# untitled.net
KiCad netlist of a schematic drawn in EAGLE
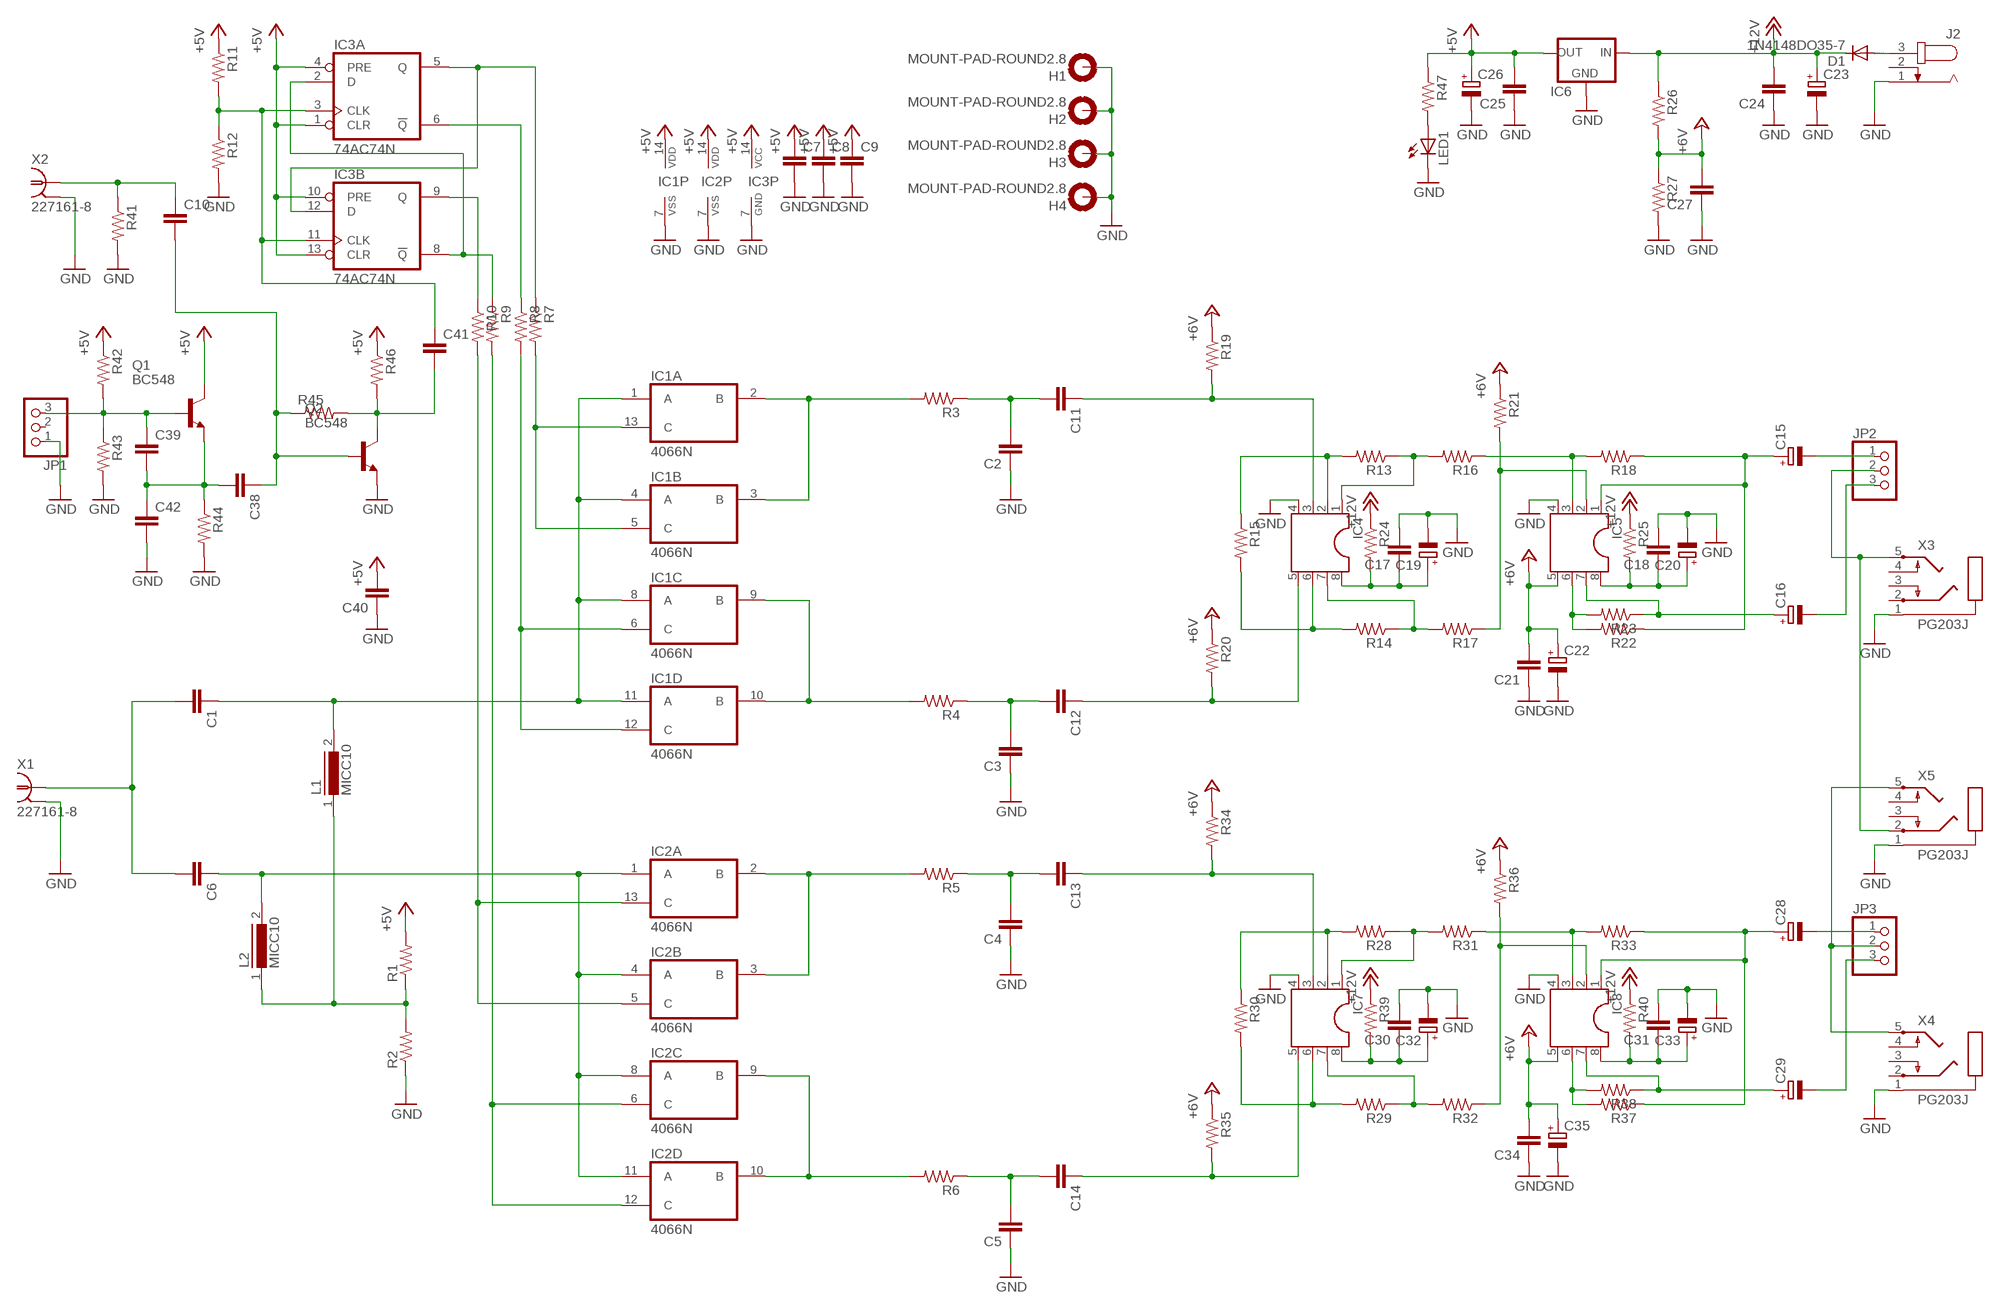
[diagram p0: schematic, sheet 1]

(export (version "E")
  (design (tool "Eeschema 10.0.6"))
  (components
    (comp (ref "C1")
      (value "C-EU050-025X075")
      (footprint "eagle-import:C050-025X075")
      (libsource (lib "eagle-import") (part "C-EU050-025X075"))
    )
    (comp (ref "C2")
      (value "C-EU050-025X075")
      (footprint "eagle-import:C050-025X075")
      (libsource (lib "eagle-import") (part "C-EU050-025X075"))
    )
    (comp (ref "C3")
      (value "C-EU050-025X075")
      (footprint "eagle-import:C050-025X075")
      (libsource (lib "eagle-import") (part "C-EU050-025X075"))
    )
    (comp (ref "C4")
      (value "C-EU050-025X075")
      (footprint "eagle-import:C050-025X075")
      (libsource (lib "eagle-import") (part "C-EU050-025X075"))
    )
    (comp (ref "C5")
      (value "C-EU050-025X075")
      (footprint "eagle-import:C050-025X075")
      (libsource (lib "eagle-import") (part "C-EU050-025X075"))
    )
    (comp (ref "C6")
      (value "C-EU050-025X075")
      (footprint "eagle-import:C050-025X075")
      (libsource (lib "eagle-import") (part "C-EU050-025X075"))
    )
    (comp (ref "C7")
      (value "C-EU050-025X075")
      (footprint "eagle-import:C050-025X075")
      (libsource (lib "eagle-import") (part "C-EU050-025X075"))
    )
    (comp (ref "C8")
      (value "C-EU050-025X075")
      (footprint "eagle-import:C050-025X075")
      (libsource (lib "eagle-import") (part "C-EU050-025X075"))
    )
    (comp (ref "C9")
      (value "C-EU050-025X075")
      (footprint "eagle-import:C050-025X075")
      (libsource (lib "eagle-import") (part "C-EU050-025X075"))
    )
    (comp (ref "C10")
      (value "C-EU050-025X075")
      (footprint "eagle-import:C050-025X075")
      (libsource (lib "eagle-import") (part "C-EU050-025X075"))
    )
    (comp (ref "C11")
      (value "C-EU050-025X075")
      (footprint "eagle-import:C050-025X075")
      (libsource (lib "eagle-import") (part "C-EU050-025X075"))
    )
    (comp (ref "C12")
      (value "C-EU050-025X075")
      (footprint "eagle-import:C050-025X075")
      (libsource (lib "eagle-import") (part "C-EU050-025X075"))
    )
    (comp (ref "C13")
      (value "C-EU050-025X075")
      (footprint "eagle-import:C050-025X075")
      (libsource (lib "eagle-import") (part "C-EU050-025X075"))
    )
    (comp (ref "C14")
      (value "C-EU050-025X075")
      (footprint "eagle-import:C050-025X075")
      (libsource (lib "eagle-import") (part "C-EU050-025X075"))
    )
    (comp (ref "C15")
      (value "CPOL-EUE5-6")
      (footprint "eagle-import:E5-6")
      (libsource (lib "eagle-import") (part "CPOL-EUE5-6"))
    )
    (comp (ref "C16")
      (value "CPOL-EUE5-6")
      (footprint "eagle-import:E5-6")
      (libsource (lib "eagle-import") (part "CPOL-EUE5-6"))
    )
    (comp (ref "C17")
      (value "C-EU050-025X075")
      (footprint "eagle-import:C050-025X075")
      (libsource (lib "eagle-import") (part "C-EU050-025X075"))
    )
    (comp (ref "C18")
      (value "C-EU050-025X075")
      (footprint "eagle-import:C050-025X075")
      (libsource (lib "eagle-import") (part "C-EU050-025X075"))
    )
    (comp (ref "C19")
      (value "CPOL-EUE5-6")
      (footprint "eagle-import:E5-6")
      (libsource (lib "eagle-import") (part "CPOL-EUE5-6"))
    )
    (comp (ref "C20")
      (value "CPOL-EUE5-6")
      (footprint "eagle-import:E5-6")
      (libsource (lib "eagle-import") (part "CPOL-EUE5-6"))
    )
    (comp (ref "C21")
      (value "C-EU050-025X075")
      (footprint "eagle-import:C050-025X075")
      (libsource (lib "eagle-import") (part "C-EU050-025X075"))
    )
    (comp (ref "C22")
      (value "CPOL-EUE5-6")
      (footprint "eagle-import:E5-6")
      (libsource (lib "eagle-import") (part "CPOL-EUE5-6"))
    )
    (comp (ref "C23")
      (value "CPOL-EUE5-6")
      (footprint "eagle-import:E5-6")
      (libsource (lib "eagle-import") (part "CPOL-EUE5-6"))
    )
    (comp (ref "C24")
      (value "C-EU050-025X075")
      (footprint "eagle-import:C050-025X075")
      (libsource (lib "eagle-import") (part "C-EU050-025X075"))
    )
    (comp (ref "C25")
      (value "C-EU050-025X075")
      (footprint "eagle-import:C050-025X075")
      (libsource (lib "eagle-import") (part "C-EU050-025X075"))
    )
    (comp (ref "C26")
      (value "CPOL-EUE5-6")
      (footprint "eagle-import:E5-6")
      (libsource (lib "eagle-import") (part "CPOL-EUE5-6"))
    )
    (comp (ref "C27")
      (value "C-EU050-025X075")
      (footprint "eagle-import:C050-025X075")
      (libsource (lib "eagle-import") (part "C-EU050-025X075"))
    )
    (comp (ref "C28")
      (value "CPOL-EUE5-6")
      (footprint "eagle-import:E5-6")
      (libsource (lib "eagle-import") (part "CPOL-EUE5-6"))
    )
    (comp (ref "C29")
      (value "CPOL-EUE5-6")
      (footprint "eagle-import:E5-6")
      (libsource (lib "eagle-import") (part "CPOL-EUE5-6"))
    )
    (comp (ref "C30")
      (value "C-EU050-025X075")
      (footprint "eagle-import:C050-025X075")
      (libsource (lib "eagle-import") (part "C-EU050-025X075"))
    )
    (comp (ref "C31")
      (value "C-EU050-025X075")
      (footprint "eagle-import:C050-025X075")
      (libsource (lib "eagle-import") (part "C-EU050-025X075"))
    )
    (comp (ref "C32")
      (value "CPOL-EUE5-6")
      (footprint "eagle-import:E5-6")
      (libsource (lib "eagle-import") (part "CPOL-EUE5-6"))
    )
    (comp (ref "C33")
      (value "CPOL-EUE5-6")
      (footprint "eagle-import:E5-6")
      (libsource (lib "eagle-import") (part "CPOL-EUE5-6"))
    )
    (comp (ref "C34")
      (value "C-EU050-025X075")
      (footprint "eagle-import:C050-025X075")
      (libsource (lib "eagle-import") (part "C-EU050-025X075"))
    )
    (comp (ref "C35")
      (value "CPOL-EUE5-6")
      (footprint "eagle-import:E5-6")
      (libsource (lib "eagle-import") (part "CPOL-EUE5-6"))
    )
    (comp (ref "C38")
      (value "C-EU050-025X075")
      (footprint "eagle-import:C050-025X075")
      (libsource (lib "eagle-import") (part "C-EU050-025X075"))
    )
    (comp (ref "C39")
      (value "C-EU025-025X050")
      (footprint "eagle-import:C025-025X050")
      (libsource (lib "eagle-import") (part "C-EU025-025X050"))
    )
    (comp (ref "C40")
      (value "C-EU050-025X075")
      (footprint "eagle-import:C050-025X075")
      (libsource (lib "eagle-import") (part "C-EU050-025X075"))
    )
    (comp (ref "C41")
      (value "C-EU075-032X103")
      (footprint "eagle-import:C075-032X103")
      (libsource (lib "eagle-import") (part "C-EU075-032X103"))
    )
    (comp (ref "C42")
      (value "C-EU025-025X050")
      (footprint "eagle-import:C025-025X050")
      (libsource (lib "eagle-import") (part "C-EU025-025X050"))
    )
    (comp (ref "D1")
      (value "1N4148DO35-7")
      (footprint "eagle-import:DO35-7")
      (libsource (lib "eagle-import") (part "1N4148DO35-7"))
    )
    (comp (ref "H1")
      (value "MOUNT-PAD-ROUND2.8")
      (footprint "eagle-import:2,8-PAD")
      (libsource (lib "eagle-import") (part "MOUNT-PAD-ROUND2.8"))
    )
    (comp (ref "H2")
      (value "MOUNT-PAD-ROUND2.8")
      (footprint "eagle-import:2,8-PAD")
      (libsource (lib "eagle-import") (part "MOUNT-PAD-ROUND2.8"))
    )
    (comp (ref "H3")
      (value "MOUNT-PAD-ROUND2.8")
      (footprint "eagle-import:2,8-PAD")
      (libsource (lib "eagle-import") (part "MOUNT-PAD-ROUND2.8"))
    )
    (comp (ref "H4")
      (value "MOUNT-PAD-ROUND2.8")
      (footprint "eagle-import:2,8-PAD")
      (libsource (lib "eagle-import") (part "MOUNT-PAD-ROUND2.8"))
    )
    (comp (ref "IC1")
      (value "4066N")
      (footprint "eagle-import:DIL14")
      (libsource (lib "eagle-import") (part "4066N"))
    )
    (comp (ref "IC2")
      (value "4066N")
      (footprint "eagle-import:DIL14")
      (libsource (lib "eagle-import") (part "4066N"))
    )
    (comp (ref "IC3")
      (value "74AC74N")
      (footprint "eagle-import:DIL14")
      (libsource (lib "eagle-import") (part "7474NAC"))
    )
    (comp (ref "IC4")
      (value "DIL8")
      (footprint "eagle-import:DIL08")
      (libsource (lib "eagle-import") (part "DIL8"))
    )
    (comp (ref "IC5")
      (value "DIL8")
      (footprint "eagle-import:DIL08")
      (libsource (lib "eagle-import") (part "DIL8"))
    )
    (comp (ref "IC6")
      (value "78XXS")
      (footprint "eagle-import:78XXS")
      (libsource (lib "eagle-import") (part "78XXS"))
    )
    (comp (ref "IC7")
      (value "DIL8")
      (footprint "eagle-import:DIL08")
      (libsource (lib "eagle-import") (part "DIL8"))
    )
    (comp (ref "IC8")
      (value "DIL8")
      (footprint "eagle-import:DIL08")
      (libsource (lib "eagle-import") (part "DIL8"))
    )
    (comp (ref "J2")
      (value "JACK-PLUG0")
      (footprint "eagle-import:SPC4077")
      (libsource (lib "eagle-import") (part "JACK-PLUG0"))
    )
    (comp (ref "JP1")
      (value "PINHD-1X3")
      (footprint "eagle-import:1X03")
      (libsource (lib "eagle-import") (part "PINHD-1X3"))
    )
    (comp (ref "JP2")
      (value "PINHD-1X3")
      (footprint "eagle-import:1X03")
      (libsource (lib "eagle-import") (part "PINHD-1X3"))
    )
    (comp (ref "JP3")
      (value "PINHD-1X3")
      (footprint "eagle-import:1X03")
      (libsource (lib "eagle-import") (part "PINHD-1X3"))
    )
    (comp (ref "L1")
      (value "MICC10")
      (footprint "eagle-import:MICC10")
      (libsource (lib "eagle-import") (part "MICC10"))
    )
    (comp (ref "L2")
      (value "MICC10")
      (footprint "eagle-import:MICC10")
      (libsource (lib "eagle-import") (part "MICC10"))
    )
    (comp (ref "LED1")
      (value "LED3MM")
      (footprint "eagle-import:LED3MM")
      (libsource (lib "eagle-import") (part "LED3MM"))
    )
    (comp (ref "Q1")
      (value "BC548")
      (footprint "eagle-import:TO92-EBC")
      (libsource (lib "eagle-import") (part "BC548"))
    )
    (comp (ref "Q2")
      (value "BC548")
      (footprint "eagle-import:TO92-EBC")
      (libsource (lib "eagle-import") (part "BC548"))
    )
    (comp (ref "R1")
      (value "R-US_0207/7")
      (footprint "eagle-import:0207_7")
      (libsource (lib "eagle-import") (part "R-US_0207/7"))
    )
    (comp (ref "R2")
      (value "R-US_0207/7")
      (footprint "eagle-import:0207_7")
      (libsource (lib "eagle-import") (part "R-US_0207/7"))
    )
    (comp (ref "R3")
      (value "R-US_0207/7")
      (footprint "eagle-import:0207_7")
      (libsource (lib "eagle-import") (part "R-US_0207/7"))
    )
    (comp (ref "R4")
      (value "R-US_0207/7")
      (footprint "eagle-import:0207_7")
      (libsource (lib "eagle-import") (part "R-US_0207/7"))
    )
    (comp (ref "R5")
      (value "R-US_0207/7")
      (footprint "eagle-import:0207_7")
      (libsource (lib "eagle-import") (part "R-US_0207/7"))
    )
    (comp (ref "R6")
      (value "R-US_0207/7")
      (footprint "eagle-import:0207_7")
      (libsource (lib "eagle-import") (part "R-US_0207/7"))
    )
    (comp (ref "R7")
      (value "R-US_0207/7")
      (footprint "eagle-import:0207_7")
      (libsource (lib "eagle-import") (part "R-US_0207/7"))
    )
    (comp (ref "R8")
      (value "R-US_0207/7")
      (footprint "eagle-import:0207_7")
      (libsource (lib "eagle-import") (part "R-US_0207/7"))
    )
    (comp (ref "R9")
      (value "R-US_0207/7")
      (footprint "eagle-import:0207_7")
      (libsource (lib "eagle-import") (part "R-US_0207/7"))
    )
    (comp (ref "R10")
      (value "R-US_0207/7")
      (footprint "eagle-import:0207_7")
      (libsource (lib "eagle-import") (part "R-US_0207/7"))
    )
    (comp (ref "R11")
      (value "R-US_0207/7")
      (footprint "eagle-import:0207_7")
      (libsource (lib "eagle-import") (part "R-US_0207/7"))
    )
    (comp (ref "R12")
      (value "R-US_0207/7")
      (footprint "eagle-import:0207_7")
      (libsource (lib "eagle-import") (part "R-US_0207/7"))
    )
    (comp (ref "R13")
      (value "R-US_0207/7")
      (footprint "eagle-import:0207_7")
      (libsource (lib "eagle-import") (part "R-US_0207/7"))
    )
    (comp (ref "R14")
      (value "R-US_0207/7")
      (footprint "eagle-import:0207_7")
      (libsource (lib "eagle-import") (part "R-US_0207/7"))
    )
    (comp (ref "R15")
      (value "R-US_0207/7")
      (footprint "eagle-import:0207_7")
      (libsource (lib "eagle-import") (part "R-US_0207/7"))
    )
    (comp (ref "R16")
      (value "R-US_0207/7")
      (footprint "eagle-import:0207_7")
      (libsource (lib "eagle-import") (part "R-US_0207/7"))
    )
    (comp (ref "R17")
      (value "R-US_0207/7")
      (footprint "eagle-import:0207_7")
      (libsource (lib "eagle-import") (part "R-US_0207/7"))
    )
    (comp (ref "R18")
      (value "R-US_0207/7")
      (footprint "eagle-import:0207_7")
      (libsource (lib "eagle-import") (part "R-US_0207/7"))
    )
    (comp (ref "R19")
      (value "R-US_0207/7")
      (footprint "eagle-import:0207_7")
      (libsource (lib "eagle-import") (part "R-US_0207/7"))
    )
    (comp (ref "R20")
      (value "R-US_0207/7")
      (footprint "eagle-import:0207_7")
      (libsource (lib "eagle-import") (part "R-US_0207/7"))
    )
    (comp (ref "R21")
      (value "R-US_0207/7")
      (footprint "eagle-import:0207_7")
      (libsource (lib "eagle-import") (part "R-US_0207/7"))
    )
    (comp (ref "R22")
      (value "R-US_0207/7")
      (footprint "eagle-import:0207_7")
      (libsource (lib "eagle-import") (part "R-US_0207/7"))
    )
    (comp (ref "R23")
      (value "R-US_0207/7")
      (footprint "eagle-import:0207_7")
      (libsource (lib "eagle-import") (part "R-US_0207/7"))
    )
    (comp (ref "R24")
      (value "R-US_0207/7")
      (footprint "eagle-import:0207_7")
      (libsource (lib "eagle-import") (part "R-US_0207/7"))
    )
    (comp (ref "R25")
      (value "R-US_0207/7")
      (footprint "eagle-import:0207_7")
      (libsource (lib "eagle-import") (part "R-US_0207/7"))
    )
    (comp (ref "R26")
      (value "R-US_0207/7")
      (footprint "eagle-import:0207_7")
      (libsource (lib "eagle-import") (part "R-US_0207/7"))
    )
    (comp (ref "R27")
      (value "R-US_0207/7")
      (footprint "eagle-import:0207_7")
      (libsource (lib "eagle-import") (part "R-US_0207/7"))
    )
    (comp (ref "R28")
      (value "R-US_0207/7")
      (footprint "eagle-import:0207_7")
      (libsource (lib "eagle-import") (part "R-US_0207/7"))
    )
    (comp (ref "R29")
      (value "R-US_0207/7")
      (footprint "eagle-import:0207_7")
      (libsource (lib "eagle-import") (part "R-US_0207/7"))
    )
    (comp (ref "R30")
      (value "R-US_0207/7")
      (footprint "eagle-import:0207_7")
      (libsource (lib "eagle-import") (part "R-US_0207/7"))
    )
    (comp (ref "R31")
      (value "R-US_0207/7")
      (footprint "eagle-import:0207_7")
      (libsource (lib "eagle-import") (part "R-US_0207/7"))
    )
    (comp (ref "R32")
      (value "R-US_0207/7")
      (footprint "eagle-import:0207_7")
      (libsource (lib "eagle-import") (part "R-US_0207/7"))
    )
    (comp (ref "R33")
      (value "R-US_0207/7")
      (footprint "eagle-import:0207_7")
      (libsource (lib "eagle-import") (part "R-US_0207/7"))
    )
    (comp (ref "R34")
      (value "R-US_0207/7")
      (footprint "eagle-import:0207_7")
      (libsource (lib "eagle-import") (part "R-US_0207/7"))
    )
    (comp (ref "R35")
      (value "R-US_0207/7")
      (footprint "eagle-import:0207_7")
      (libsource (lib "eagle-import") (part "R-US_0207/7"))
    )
    (comp (ref "R36")
      (value "R-US_0207/7")
      (footprint "eagle-import:0207_7")
      (libsource (lib "eagle-import") (part "R-US_0207/7"))
    )
    (comp (ref "R37")
      (value "R-US_0207/7")
      (footprint "eagle-import:0207_7")
      (libsource (lib "eagle-import") (part "R-US_0207/7"))
    )
    (comp (ref "R38")
      (value "R-US_0207/7")
      (footprint "eagle-import:0207_7")
      (libsource (lib "eagle-import") (part "R-US_0207/7"))
    )
    (comp (ref "R39")
      (value "R-US_0207/7")
      (footprint "eagle-import:0207_7")
      (libsource (lib "eagle-import") (part "R-US_0207/7"))
    )
    (comp (ref "R40")
      (value "R-US_0207/7")
      (footprint "eagle-import:0207_7")
      (libsource (lib "eagle-import") (part "R-US_0207/7"))
    )
    (comp (ref "R41")
      (value "R-US_0207/7")
      (footprint "eagle-import:0207_7")
      (libsource (lib "eagle-import") (part "R-US_0207/7"))
    )
    (comp (ref "R42")
      (value "R-US_0207/7")
      (footprint "eagle-import:0207_7")
      (libsource (lib "eagle-import") (part "R-US_0207/7"))
    )
    (comp (ref "R43")
      (value "R-US_0207/7")
      (footprint "eagle-import:0207_7")
      (libsource (lib "eagle-import") (part "R-US_0207/7"))
    )
    (comp (ref "R44")
      (value "R-US_0207/7")
      (footprint "eagle-import:0207_7")
      (libsource (lib "eagle-import") (part "R-US_0207/7"))
    )
    (comp (ref "R45")
      (value "R-US_0207/7")
      (footprint "eagle-import:0207_7")
      (libsource (lib "eagle-import") (part "R-US_0207/7"))
    )
    (comp (ref "R46")
      (value "R-US_0207/7")
      (footprint "eagle-import:0207_7")
      (libsource (lib "eagle-import") (part "R-US_0207/7"))
    )
    (comp (ref "R47")
      (value "R-US_0207/7")
      (footprint "eagle-import:0207_7")
      (libsource (lib "eagle-import") (part "R-US_0207/7"))
    )
    (comp (ref "X1")
      (value "227161-8")
      (footprint "eagle-import:AMP_227161")
      (libsource (lib "eagle-import") (part "?227161-8"))
    )
    (comp (ref "X2")
      (value "227161-8")
      (footprint "eagle-import:AMP_227161")
      (libsource (lib "eagle-import") (part "?227161-8"))
    )
    (comp (ref "X3")
      (value "PG203J")
      (footprint "eagle-import:PG203J")
      (libsource (lib "eagle-import") (part "PG203J"))
    )
    (comp (ref "X4")
      (value "PG203J")
      (footprint "eagle-import:PG203J")
      (libsource (lib "eagle-import") (part "PG203J"))
    )
    (comp (ref "X5")
      (value "PG203J")
      (footprint "eagle-import:PG203J")
      (libsource (lib "eagle-import") (part "PG203J"))
    )
  )
  (nets
    (net (code "1") (name "+5V") (class "Default")
      (node (ref "C25") (pin "2") (pinfunction "2_2") (pintype "passive"))
      (node (ref "C26") (pin "+") (pinfunction "+_+") (pintype "passive"))
      (node (ref "C40") (pin "2") (pinfunction "2_2") (pintype "passive"))
      (node (ref "C7") (pin "1") (pinfunction "1_1") (pintype "passive"))
      (node (ref "C8") (pin "1") (pinfunction "1_1") (pintype "passive"))
      (node (ref "C9") (pin "1") (pinfunction "1_1") (pintype "passive"))
      (node (ref "IC1") (pin "14") (pinfunction "VDD_14") (pintype "power_in"))
      (node (ref "IC2") (pin "14") (pinfunction "VDD_14") (pintype "power_in"))
      (node (ref "IC3") (pin "1") (pinfunction "CLR_1") (pintype "input"))
      (node (ref "IC3") (pin "10") (pinfunction "PRE_10") (pintype "input"))
      (node (ref "IC3") (pin "13") (pinfunction "CLR_13") (pintype "input"))
      (node (ref "IC3") (pin "14") (pinfunction "VCC_14") (pintype "power_in"))
      (node (ref "IC3") (pin "4") (pinfunction "PRE_4") (pintype "input"))
      (node (ref "IC6") (pin "OUT") (pinfunction "OUT_OUT") (pintype "passive"))
      (node (ref "Q1") (pin "C") (pinfunction "C_C") (pintype "passive"))
      (node (ref "R1") (pin "2") (pinfunction "2_2") (pintype "passive"))
      (node (ref "R11") (pin "1") (pinfunction "1_1") (pintype "passive"))
      (node (ref "R42") (pin "1") (pinfunction "1_1") (pintype "passive"))
      (node (ref "R46") (pin "1") (pinfunction "1_1") (pintype "passive"))
      (node (ref "R47") (pin "1") (pinfunction "1_1") (pintype "passive"))
    )
    (net (code "2") (name "+6V") (class "Default")
      (node (ref "C21") (pin "2") (pinfunction "2_2") (pintype "passive"))
      (node (ref "C22") (pin "+") (pinfunction "+_+") (pintype "passive"))
      (node (ref "C27") (pin "2") (pinfunction "2_2") (pintype "passive"))
      (node (ref "C34") (pin "2") (pinfunction "2_2") (pintype "passive"))
      (node (ref "C35") (pin "+") (pinfunction "+_+") (pintype "passive"))
      (node (ref "IC5") (pin "5") (pinfunction "5_5") (pintype "passive"))
      (node (ref "IC8") (pin "5") (pinfunction "5_5") (pintype "passive"))
      (node (ref "R19") (pin "1") (pinfunction "1_1") (pintype "passive"))
      (node (ref "R20") (pin "1") (pinfunction "1_1") (pintype "passive"))
      (node (ref "R21") (pin "1") (pinfunction "1_1") (pintype "passive"))
      (node (ref "R26") (pin "2") (pinfunction "2_2") (pintype "passive"))
      (node (ref "R27") (pin "1") (pinfunction "1_1") (pintype "passive"))
      (node (ref "R34") (pin "1") (pinfunction "1_1") (pintype "passive"))
      (node (ref "R35") (pin "1") (pinfunction "1_1") (pintype "passive"))
      (node (ref "R36") (pin "1") (pinfunction "1_1") (pintype "passive"))
    )
    (net (code "3") (name "+12V") (class "Default")
      (node (ref "C23") (pin "+") (pinfunction "+_+") (pintype "passive"))
      (node (ref "C24") (pin "2") (pinfunction "2_2") (pintype "passive"))
      (node (ref "D1") (pin "C") (pinfunction "C_C") (pintype "passive"))
      (node (ref "IC6") (pin "IN") (pinfunction "IN_IN") (pintype "input"))
      (node (ref "R24") (pin "1") (pinfunction "1_1") (pintype "passive"))
      (node (ref "R25") (pin "1") (pinfunction "1_1") (pintype "passive"))
      (node (ref "R26") (pin "1") (pinfunction "1_1") (pintype "passive"))
      (node (ref "R39") (pin "1") (pinfunction "1_1") (pintype "passive"))
      (node (ref "R40") (pin "1") (pinfunction "1_1") (pintype "passive"))
    )
    (net (code "4") (name "GND") (class "Default")
      (node (ref "C17") (pin "2") (pinfunction "2_2") (pintype "passive"))
      (node (ref "C18") (pin "2") (pinfunction "2_2") (pintype "passive"))
      (node (ref "C19") (pin "-") (pinfunction "-_-") (pintype "passive"))
      (node (ref "C2") (pin "1") (pinfunction "1_1") (pintype "passive"))
      (node (ref "C20") (pin "-") (pinfunction "-_-") (pintype "passive"))
      (node (ref "C21") (pin "1") (pinfunction "1_1") (pintype "passive"))
      (node (ref "C22") (pin "-") (pinfunction "-_-") (pintype "passive"))
      (node (ref "C23") (pin "-") (pinfunction "-_-") (pintype "passive"))
      (node (ref "C24") (pin "1") (pinfunction "1_1") (pintype "passive"))
      (node (ref "C25") (pin "1") (pinfunction "1_1") (pintype "passive"))
      (node (ref "C26") (pin "-") (pinfunction "-_-") (pintype "passive"))
      (node (ref "C27") (pin "1") (pinfunction "1_1") (pintype "passive"))
      (node (ref "C3") (pin "1") (pinfunction "1_1") (pintype "passive"))
      (node (ref "C30") (pin "2") (pinfunction "2_2") (pintype "passive"))
      (node (ref "C31") (pin "2") (pinfunction "2_2") (pintype "passive"))
      (node (ref "C32") (pin "-") (pinfunction "-_-") (pintype "passive"))
      (node (ref "C33") (pin "-") (pinfunction "-_-") (pintype "passive"))
      (node (ref "C34") (pin "1") (pinfunction "1_1") (pintype "passive"))
      (node (ref "C35") (pin "-") (pinfunction "-_-") (pintype "passive"))
      (node (ref "C4") (pin "1") (pinfunction "1_1") (pintype "passive"))
      (node (ref "C40") (pin "1") (pinfunction "1_1") (pintype "passive"))
      (node (ref "C42") (pin "2") (pinfunction "2_2") (pintype "passive"))
      (node (ref "C5") (pin "1") (pinfunction "1_1") (pintype "passive"))
      (node (ref "C7") (pin "2") (pinfunction "2_2") (pintype "passive"))
      (node (ref "C8") (pin "2") (pinfunction "2_2") (pintype "passive"))
      (node (ref "C9") (pin "2") (pinfunction "2_2") (pintype "passive"))
      (node (ref "H1") (pin "B2,8") (pinfunction "MOUNT_B2,8") (pintype "passive"))
      (node (ref "H2") (pin "B2,8") (pinfunction "MOUNT_B2,8") (pintype "passive"))
      (node (ref "H3") (pin "B2,8") (pinfunction "MOUNT_B2,8") (pintype "passive"))
      (node (ref "H4") (pin "B2,8") (pinfunction "MOUNT_B2,8") (pintype "passive"))
      (node (ref "IC1") (pin "7") (pinfunction "VSS_7") (pintype "power_in"))
      (node (ref "IC2") (pin "7") (pinfunction "VSS_7") (pintype "power_in"))
      (node (ref "IC3") (pin "7") (pinfunction "GND_7") (pintype "power_in"))
      (node (ref "IC4") (pin "4") (pinfunction "4_4") (pintype "passive"))
      (node (ref "IC5") (pin "4") (pinfunction "4_4") (pintype "passive"))
      (node (ref "IC6") (pin "GND") (pinfunction "GND_GND") (pintype "input"))
      (node (ref "IC7") (pin "4") (pinfunction "4_4") (pintype "passive"))
      (node (ref "IC8") (pin "4") (pinfunction "4_4") (pintype "passive"))
      (node (ref "J2") (pin "1") (pinfunction "1_1") (pintype "passive"))
      (node (ref "JP1") (pin "1") (pinfunction "1_1") (pintype "passive"))
      (node (ref "LED1") (pin "K") (pinfunction "C_K") (pintype "passive"))
      (node (ref "Q2") (pin "E") (pinfunction "E_E") (pintype "passive"))
      (node (ref "R12") (pin "2") (pinfunction "2_2") (pintype "passive"))
      (node (ref "R2") (pin "1") (pinfunction "1_1") (pintype "passive"))
      (node (ref "R27") (pin "2") (pinfunction "2_2") (pintype "passive"))
      (node (ref "R41") (pin "2") (pinfunction "2_2") (pintype "passive"))
      (node (ref "R43") (pin "2") (pinfunction "2_2") (pintype "passive"))
      (node (ref "R44") (pin "2") (pinfunction "2_2") (pintype "passive"))
      (node (ref "X1") (pin "2") (pinfunction "2_2") (pintype "passive"))
      (node (ref "X2") (pin "2") (pinfunction "2_2") (pintype "passive"))
      (node (ref "X3") (pin "1") (pinfunction "1_1") (pintype "passive"))
      (node (ref "X4") (pin "1") (pinfunction "1_1") (pintype "passive"))
      (node (ref "X5") (pin "1") (pinfunction "1_1") (pintype "passive"))
    )
    (net (code "5") (name "Net-(C1-Pad2)") (class "Default")
      (node (ref "C1") (pin "2") (pinfunction "2_2") (pintype "passive"))
      (node (ref "C6") (pin "2") (pinfunction "2_2") (pintype "passive"))
      (node (ref "X1") (pin "1") (pinfunction "1_1") (pintype "passive"))
    )
    (net (code "6") (name "Net-(C10-Pad1)") (class "Default")
      (node (ref "C10") (pin "1") (pinfunction "1_1") (pintype "passive"))
      (node (ref "R41") (pin "1") (pinfunction "1_1") (pintype "passive"))
      (node (ref "X2") (pin "1") (pinfunction "1_1") (pintype "passive"))
    )
    (net (code "7") (name "Net-(C10-Pad2)") (class "Default")
      (node (ref "C10") (pin "2") (pinfunction "2_2") (pintype "passive"))
      (node (ref "C38") (pin "1") (pinfunction "1_1") (pintype "passive"))
      (node (ref "Q2") (pin "B") (pinfunction "B_B") (pintype "passive"))
      (node (ref "R45") (pin "1") (pinfunction "1_1") (pintype "passive"))
    )
    (net (code "8") (name "Net-(C11-Pad1)") (class "Default")
      (node (ref "C11") (pin "1") (pinfunction "1_1") (pintype "passive"))
      (node (ref "IC4") (pin "3") (pinfunction "3_3") (pintype "passive"))
      (node (ref "R19") (pin "2") (pinfunction "2_2") (pintype "passive"))
    )
    (net (code "9") (name "Net-(C11-Pad2)") (class "Default")
      (node (ref "C11") (pin "2") (pinfunction "2_2") (pintype "passive"))
      (node (ref "C2") (pin "2") (pinfunction "2_2") (pintype "passive"))
      (node (ref "R3") (pin "1") (pinfunction "1_1") (pintype "passive"))
    )
    (net (code "10") (name "Net-(C12-Pad1)") (class "Default")
      (node (ref "C12") (pin "1") (pinfunction "1_1") (pintype "passive"))
      (node (ref "IC4") (pin "5") (pinfunction "5_5") (pintype "passive"))
      (node (ref "R20") (pin "2") (pinfunction "2_2") (pintype "passive"))
    )
    (net (code "11") (name "Net-(C12-Pad2)") (class "Default")
      (node (ref "C12") (pin "2") (pinfunction "2_2") (pintype "passive"))
      (node (ref "C3") (pin "2") (pinfunction "2_2") (pintype "passive"))
      (node (ref "R4") (pin "1") (pinfunction "1_1") (pintype "passive"))
    )
    (net (code "12") (name "Net-(C13-Pad1)") (class "Default")
      (node (ref "C13") (pin "1") (pinfunction "1_1") (pintype "passive"))
      (node (ref "IC7") (pin "3") (pinfunction "3_3") (pintype "passive"))
      (node (ref "R34") (pin "2") (pinfunction "2_2") (pintype "passive"))
    )
    (net (code "13") (name "Net-(C13-Pad2)") (class "Default")
      (node (ref "C13") (pin "2") (pinfunction "2_2") (pintype "passive"))
      (node (ref "C4") (pin "2") (pinfunction "2_2") (pintype "passive"))
      (node (ref "R5") (pin "1") (pinfunction "1_1") (pintype "passive"))
    )
    (net (code "14") (name "Net-(C14-Pad1)") (class "Default")
      (node (ref "C14") (pin "1") (pinfunction "1_1") (pintype "passive"))
      (node (ref "IC7") (pin "5") (pinfunction "5_5") (pintype "passive"))
      (node (ref "R35") (pin "2") (pinfunction "2_2") (pintype "passive"))
    )
    (net (code "15") (name "Net-(C14-Pad2)") (class "Default")
      (node (ref "C14") (pin "2") (pinfunction "2_2") (pintype "passive"))
      (node (ref "C5") (pin "2") (pinfunction "2_2") (pintype "passive"))
      (node (ref "R6") (pin "1") (pinfunction "1_1") (pintype "passive"))
    )
    (net (code "16") (name "Net-(C15-Pad+)") (class "Default")
      (node (ref "C15") (pin "+") (pinfunction "+_+") (pintype "passive"))
      (node (ref "IC5") (pin "1") (pinfunction "1_1") (pintype "passive"))
      (node (ref "R18") (pin "1") (pinfunction "1_1") (pintype "passive"))
      (node (ref "R22") (pin "1") (pinfunction "1_1") (pintype "passive"))
    )
    (net (code "17") (name "Net-(C15-Pad-)") (class "Default")
      (node (ref "C15") (pin "-") (pinfunction "-_-") (pintype "passive"))
      (node (ref "JP2") (pin "1") (pinfunction "1_1") (pintype "passive"))
    )
    (net (code "18") (name "Net-(C16-Pad+)") (class "Default")
      (node (ref "C16") (pin "+") (pinfunction "+_+") (pintype "passive"))
      (node (ref "IC5") (pin "7") (pinfunction "7_7") (pintype "passive"))
      (node (ref "R23") (pin "1") (pinfunction "1_1") (pintype "passive"))
    )
    (net (code "19") (name "Net-(C16-Pad-)") (class "Default")
      (node (ref "C16") (pin "-") (pinfunction "-_-") (pintype "passive"))
      (node (ref "JP2") (pin "3") (pinfunction "3_3") (pintype "passive"))
    )
    (net (code "20") (name "Net-(C17-Pad1)") (class "Default")
      (node (ref "C17") (pin "1") (pinfunction "1_1") (pintype "passive"))
      (node (ref "C19") (pin "+") (pinfunction "+_+") (pintype "passive"))
      (node (ref "IC4") (pin "8") (pinfunction "8_8") (pintype "passive"))
      (node (ref "R24") (pin "2") (pinfunction "2_2") (pintype "passive"))
    )
    (net (code "21") (name "Net-(C18-Pad1)") (class "Default")
      (node (ref "C18") (pin "1") (pinfunction "1_1") (pintype "passive"))
      (node (ref "C20") (pin "+") (pinfunction "+_+") (pintype "passive"))
      (node (ref "IC5") (pin "8") (pinfunction "8_8") (pintype "passive"))
      (node (ref "R25") (pin "2") (pinfunction "2_2") (pintype "passive"))
    )
    (net (code "22") (name "Net-(C28-Pad+)") (class "Default")
      (node (ref "C28") (pin "+") (pinfunction "+_+") (pintype "passive"))
      (node (ref "IC8") (pin "1") (pinfunction "1_1") (pintype "passive"))
      (node (ref "R33") (pin "1") (pinfunction "1_1") (pintype "passive"))
      (node (ref "R37") (pin "1") (pinfunction "1_1") (pintype "passive"))
    )
    (net (code "23") (name "Net-(C28-Pad-)") (class "Default")
      (node (ref "C28") (pin "-") (pinfunction "-_-") (pintype "passive"))
      (node (ref "JP3") (pin "1") (pinfunction "1_1") (pintype "passive"))
    )
    (net (code "24") (name "Net-(C29-Pad+)") (class "Default")
      (node (ref "C29") (pin "+") (pinfunction "+_+") (pintype "passive"))
      (node (ref "IC8") (pin "7") (pinfunction "7_7") (pintype "passive"))
      (node (ref "R38") (pin "1") (pinfunction "1_1") (pintype "passive"))
    )
    (net (code "25") (name "Net-(C29-Pad-)") (class "Default")
      (node (ref "C29") (pin "-") (pinfunction "-_-") (pintype "passive"))
      (node (ref "JP3") (pin "3") (pinfunction "3_3") (pintype "passive"))
    )
    (net (code "26") (name "Net-(C30-Pad1)") (class "Default")
      (node (ref "C30") (pin "1") (pinfunction "1_1") (pintype "passive"))
      (node (ref "C32") (pin "+") (pinfunction "+_+") (pintype "passive"))
      (node (ref "IC7") (pin "8") (pinfunction "8_8") (pintype "passive"))
      (node (ref "R39") (pin "2") (pinfunction "2_2") (pintype "passive"))
    )
    (net (code "27") (name "Net-(C31-Pad1)") (class "Default")
      (node (ref "C31") (pin "1") (pinfunction "1_1") (pintype "passive"))
      (node (ref "C33") (pin "+") (pinfunction "+_+") (pintype "passive"))
      (node (ref "IC8") (pin "8") (pinfunction "8_8") (pintype "passive"))
      (node (ref "R40") (pin "2") (pinfunction "2_2") (pintype "passive"))
    )
    (net (code "28") (name "Net-(C38-Pad2)") (class "Default")
      (node (ref "C38") (pin "2") (pinfunction "2_2") (pintype "passive"))
      (node (ref "C39") (pin "2") (pinfunction "2_2") (pintype "passive"))
      (node (ref "C42") (pin "1") (pinfunction "1_1") (pintype "passive"))
      (node (ref "Q1") (pin "E") (pinfunction "E_E") (pintype "passive"))
      (node (ref "R44") (pin "1") (pinfunction "1_1") (pintype "passive"))
    )
    (net (code "29") (name "Net-(C39-Pad1)") (class "Default")
      (node (ref "C39") (pin "1") (pinfunction "1_1") (pintype "passive"))
      (node (ref "JP1") (pin "3") (pinfunction "3_3") (pintype "passive"))
      (node (ref "Q1") (pin "B") (pinfunction "B_B") (pintype "passive"))
      (node (ref "R42") (pin "2") (pinfunction "2_2") (pintype "passive"))
      (node (ref "R43") (pin "1") (pinfunction "1_1") (pintype "passive"))
    )
    (net (code "30") (name "Net-(C41-Pad2)") (class "Default")
      (node (ref "C41") (pin "2") (pinfunction "2_2") (pintype "passive"))
      (node (ref "Q2") (pin "C") (pinfunction "C_C") (pintype "passive"))
      (node (ref "R45") (pin "2") (pinfunction "2_2") (pintype "passive"))
      (node (ref "R46") (pin "2") (pinfunction "2_2") (pintype "passive"))
    )
    (net (code "31") (name "Net-(D1-PadA)") (class "Default")
      (node (ref "D1") (pin "A") (pinfunction "A_A") (pintype "passive"))
      (node (ref "J2") (pin "3") (pinfunction "3_3") (pintype "passive"))
    )
    (net (code "32") (name "Net-(IC1A-A)") (class "Default")
      (node (ref "C1") (pin "1") (pinfunction "1_1") (pintype "passive"))
      (node (ref "IC1") (pin "1") (pinfunction "A_1") (pintype "tri_state"))
      (node (ref "IC1") (pin "11") (pinfunction "A_11") (pintype "tri_state"))
      (node (ref "IC1") (pin "4") (pinfunction "A_4") (pintype "tri_state"))
      (node (ref "IC1") (pin "8") (pinfunction "A_8") (pintype "tri_state"))
      (node (ref "L1") (pin "2") (pinfunction "2_2") (pintype "passive"))
    )
    (net (code "33") (name "Net-(IC1A-B)") (class "Default")
      (node (ref "IC1") (pin "2") (pinfunction "B_2") (pintype "tri_state"))
      (node (ref "IC1") (pin "3") (pinfunction "B_3") (pintype "tri_state"))
      (node (ref "R3") (pin "2") (pinfunction "2_2") (pintype "passive"))
    )
    (net (code "34") (name "Net-(IC1A-C)") (class "Default")
      (node (ref "IC1") (pin "13") (pinfunction "C_13") (pintype "input"))
      (node (ref "IC1") (pin "5") (pinfunction "C_5") (pintype "input"))
      (node (ref "R7") (pin "2") (pinfunction "2_2") (pintype "passive"))
    )
    (net (code "35") (name "Net-(IC1C-B)") (class "Default")
      (node (ref "IC1") (pin "10") (pinfunction "B_10") (pintype "tri_state"))
      (node (ref "IC1") (pin "9") (pinfunction "B_9") (pintype "tri_state"))
      (node (ref "R4") (pin "2") (pinfunction "2_2") (pintype "passive"))
    )
    (net (code "36") (name "Net-(IC1C-C)") (class "Default")
      (node (ref "IC1") (pin "12") (pinfunction "C_12") (pintype "input"))
      (node (ref "IC1") (pin "6") (pinfunction "C_6") (pintype "input"))
      (node (ref "R8") (pin "2") (pinfunction "2_2") (pintype "passive"))
    )
    (net (code "37") (name "Net-(IC2A-A)") (class "Default")
      (node (ref "C6") (pin "1") (pinfunction "1_1") (pintype "passive"))
      (node (ref "IC2") (pin "1") (pinfunction "A_1") (pintype "tri_state"))
      (node (ref "IC2") (pin "11") (pinfunction "A_11") (pintype "tri_state"))
      (node (ref "IC2") (pin "4") (pinfunction "A_4") (pintype "tri_state"))
      (node (ref "IC2") (pin "8") (pinfunction "A_8") (pintype "tri_state"))
      (node (ref "L2") (pin "2") (pinfunction "2_2") (pintype "passive"))
    )
    (net (code "38") (name "Net-(IC2A-B)") (class "Default")
      (node (ref "IC2") (pin "2") (pinfunction "B_2") (pintype "tri_state"))
      (node (ref "IC2") (pin "3") (pinfunction "B_3") (pintype "tri_state"))
      (node (ref "R5") (pin "2") (pinfunction "2_2") (pintype "passive"))
    )
    (net (code "39") (name "Net-(IC2A-C)") (class "Default")
      (node (ref "IC2") (pin "13") (pinfunction "C_13") (pintype "input"))
      (node (ref "IC2") (pin "5") (pinfunction "C_5") (pintype "input"))
      (node (ref "R10") (pin "2") (pinfunction "2_2") (pintype "passive"))
    )
    (net (code "40") (name "Net-(IC2C-B)") (class "Default")
      (node (ref "IC2") (pin "10") (pinfunction "B_10") (pintype "tri_state"))
      (node (ref "IC2") (pin "9") (pinfunction "B_9") (pintype "tri_state"))
      (node (ref "R6") (pin "2") (pinfunction "2_2") (pintype "passive"))
    )
    (net (code "41") (name "Net-(IC2C-C)") (class "Default")
      (node (ref "IC2") (pin "12") (pinfunction "C_12") (pintype "input"))
      (node (ref "IC2") (pin "6") (pinfunction "C_6") (pintype "input"))
      (node (ref "R9") (pin "2") (pinfunction "2_2") (pintype "passive"))
    )
    (net (code "42") (name "Net-(IC3A-CLK)") (class "Default")
      (node (ref "C41") (pin "1") (pinfunction "1_1") (pintype "passive"))
      (node (ref "IC3") (pin "11") (pinfunction "CLK_11") (pintype "input"))
      (node (ref "IC3") (pin "3") (pinfunction "CLK_3") (pintype "input"))
      (node (ref "R11") (pin "2") (pinfunction "2_2") (pintype "passive"))
      (node (ref "R12") (pin "1") (pinfunction "1_1") (pintype "passive"))
    )
    (net (code "43") (name "Net-(IC3A-D)") (class "Default")
      (node (ref "IC3") (pin "2") (pinfunction "D_2") (pintype "input"))
      (node (ref "IC3") (pin "8") (pinfunction "~{Q}_8") (pintype "output"))
      (node (ref "R9") (pin "1") (pinfunction "1_1") (pintype "passive"))
    )
    (net (code "44") (name "Net-(IC3A-Q)") (class "Default")
      (node (ref "IC3") (pin "12") (pinfunction "D_12") (pintype "input"))
      (node (ref "IC3") (pin "5") (pinfunction "Q_5") (pintype "output"))
      (node (ref "R7") (pin "1") (pinfunction "1_1") (pintype "passive"))
    )
    (net (code "45") (name "Net-(IC3A-~{Q})") (class "Default")
      (node (ref "IC3") (pin "6") (pinfunction "~{Q}_6") (pintype "output"))
      (node (ref "R8") (pin "1") (pinfunction "1_1") (pintype "passive"))
    )
    (net (code "46") (name "Net-(IC3B-Q)") (class "Default")
      (node (ref "IC3") (pin "9") (pinfunction "Q_9") (pintype "output"))
      (node (ref "R10") (pin "1") (pinfunction "1_1") (pintype "passive"))
    )
    (net (code "47") (name "Net-(IC4-Pad1)") (class "Default")
      (node (ref "IC4") (pin "1") (pinfunction "1_1") (pintype "passive"))
      (node (ref "R13") (pin "1") (pinfunction "1_1") (pintype "passive"))
      (node (ref "R16") (pin "2") (pinfunction "2_2") (pintype "passive"))
    )
    (net (code "48") (name "Net-(IC4-Pad2)") (class "Default")
      (node (ref "IC4") (pin "2") (pinfunction "2_2") (pintype "passive"))
      (node (ref "R13") (pin "2") (pinfunction "2_2") (pintype "passive"))
      (node (ref "R15") (pin "1") (pinfunction "1_1") (pintype "passive"))
    )
    (net (code "49") (name "Net-(IC4-Pad6)") (class "Default")
      (node (ref "IC4") (pin "6") (pinfunction "6_6") (pintype "passive"))
      (node (ref "R14") (pin "2") (pinfunction "2_2") (pintype "passive"))
      (node (ref "R15") (pin "2") (pinfunction "2_2") (pintype "passive"))
    )
    (net (code "50") (name "Net-(IC4-Pad7)") (class "Default")
      (node (ref "IC4") (pin "7") (pinfunction "7_7") (pintype "passive"))
      (node (ref "R14") (pin "1") (pinfunction "1_1") (pintype "passive"))
      (node (ref "R17") (pin "2") (pinfunction "2_2") (pintype "passive"))
    )
    (net (code "51") (name "Net-(IC5-Pad2)") (class "Default")
      (node (ref "IC5") (pin "2") (pinfunction "2_2") (pintype "passive"))
      (node (ref "R17") (pin "1") (pinfunction "1_1") (pintype "passive"))
      (node (ref "R21") (pin "2") (pinfunction "2_2") (pintype "passive"))
    )
    (net (code "52") (name "Net-(IC5-Pad3)") (class "Default")
      (node (ref "IC5") (pin "3") (pinfunction "3_3") (pintype "passive"))
      (node (ref "R16") (pin "1") (pinfunction "1_1") (pintype "passive"))
      (node (ref "R18") (pin "2") (pinfunction "2_2") (pintype "passive"))
    )
    (net (code "53") (name "Net-(IC5-Pad6)") (class "Default")
      (node (ref "IC5") (pin "6") (pinfunction "6_6") (pintype "passive"))
      (node (ref "R22") (pin "2") (pinfunction "2_2") (pintype "passive"))
      (node (ref "R23") (pin "2") (pinfunction "2_2") (pintype "passive"))
    )
    (net (code "54") (name "Net-(IC7-Pad1)") (class "Default")
      (node (ref "IC7") (pin "1") (pinfunction "1_1") (pintype "passive"))
      (node (ref "R28") (pin "1") (pinfunction "1_1") (pintype "passive"))
      (node (ref "R31") (pin "2") (pinfunction "2_2") (pintype "passive"))
    )
    (net (code "55") (name "Net-(IC7-Pad2)") (class "Default")
      (node (ref "IC7") (pin "2") (pinfunction "2_2") (pintype "passive"))
      (node (ref "R28") (pin "2") (pinfunction "2_2") (pintype "passive"))
      (node (ref "R30") (pin "1") (pinfunction "1_1") (pintype "passive"))
    )
    (net (code "56") (name "Net-(IC7-Pad6)") (class "Default")
      (node (ref "IC7") (pin "6") (pinfunction "6_6") (pintype "passive"))
      (node (ref "R29") (pin "2") (pinfunction "2_2") (pintype "passive"))
      (node (ref "R30") (pin "2") (pinfunction "2_2") (pintype "passive"))
    )
    (net (code "57") (name "Net-(IC7-Pad7)") (class "Default")
      (node (ref "IC7") (pin "7") (pinfunction "7_7") (pintype "passive"))
      (node (ref "R29") (pin "1") (pinfunction "1_1") (pintype "passive"))
      (node (ref "R32") (pin "2") (pinfunction "2_2") (pintype "passive"))
    )
    (net (code "58") (name "Net-(IC8-Pad2)") (class "Default")
      (node (ref "IC8") (pin "2") (pinfunction "2_2") (pintype "passive"))
      (node (ref "R32") (pin "1") (pinfunction "1_1") (pintype "passive"))
      (node (ref "R36") (pin "2") (pinfunction "2_2") (pintype "passive"))
    )
    (net (code "59") (name "Net-(IC8-Pad3)") (class "Default")
      (node (ref "IC8") (pin "3") (pinfunction "3_3") (pintype "passive"))
      (node (ref "R31") (pin "1") (pinfunction "1_1") (pintype "passive"))
      (node (ref "R33") (pin "2") (pinfunction "2_2") (pintype "passive"))
    )
    (net (code "60") (name "Net-(IC8-Pad6)") (class "Default")
      (node (ref "IC8") (pin "6") (pinfunction "6_6") (pintype "passive"))
      (node (ref "R37") (pin "2") (pinfunction "2_2") (pintype "passive"))
      (node (ref "R38") (pin "2") (pinfunction "2_2") (pintype "passive"))
    )
    (net (code "61") (name "Net-(JP2-Pad2)") (class "Default")
      (node (ref "JP2") (pin "2") (pinfunction "2_2") (pintype "passive"))
      (node (ref "X3") (pin "5") (pinfunction "5_5") (pintype "passive"))
      (node (ref "X5") (pin "2") (pinfunction "2_2") (pintype "passive"))
    )
    (net (code "62") (name "Net-(JP3-Pad2)") (class "Default")
      (node (ref "JP3") (pin "2") (pinfunction "2_2") (pintype "passive"))
      (node (ref "X4") (pin "5") (pinfunction "5_5") (pintype "passive"))
      (node (ref "X5") (pin "5") (pinfunction "5_5") (pintype "passive"))
    )
    (net (code "63") (name "Net-(L1-Pad1)") (class "Default")
      (node (ref "L1") (pin "1") (pinfunction "1_1") (pintype "passive"))
      (node (ref "L2") (pin "1") (pinfunction "1_1") (pintype "passive"))
      (node (ref "R1") (pin "1") (pinfunction "1_1") (pintype "passive"))
      (node (ref "R2") (pin "2") (pinfunction "2_2") (pintype "passive"))
    )
    (net (code "64") (name "Net-(LED1-PadA)") (class "Default")
      (node (ref "LED1") (pin "A") (pinfunction "A_A") (pintype "passive"))
      (node (ref "R47") (pin "2") (pinfunction "2_2") (pintype "passive"))
    )
    (net (code "65") (name "unconnected-(J2-Pad2)") (class "Default")
      (node (ref "J2") (pin "2") (pinfunction "2_2") (pintype "passive"))
    )
    (net (code "66") (name "unconnected-(JP1-Pad2)") (class "Default")
      (node (ref "JP1") (pin "2") (pinfunction "2_2") (pintype "passive"))
    )
    (net (code "67") (name "unconnected-(X3-Pad2)") (class "Default")
      (node (ref "X3") (pin "2") (pinfunction "2_2") (pintype "passive"))
    )
    (net (code "68") (name "unconnected-(X3-Pad3)") (class "Default")
      (node (ref "X3") (pin "3") (pinfunction "3_3") (pintype "passive"))
    )
    (net (code "69") (name "unconnected-(X3-Pad4)") (class "Default")
      (node (ref "X3") (pin "4") (pinfunction "4_4") (pintype "passive"))
    )
    (net (code "70") (name "unconnected-(X4-Pad2)") (class "Default")
      (node (ref "X4") (pin "2") (pinfunction "2_2") (pintype "passive"))
    )
    (net (code "71") (name "unconnected-(X4-Pad3)") (class "Default")
      (node (ref "X4") (pin "3") (pinfunction "3_3") (pintype "passive"))
    )
    (net (code "72") (name "unconnected-(X4-Pad4)") (class "Default")
      (node (ref "X4") (pin "4") (pinfunction "4_4") (pintype "passive"))
    )
    (net (code "73") (name "unconnected-(X5-Pad3)") (class "Default")
      (node (ref "X5") (pin "3") (pinfunction "3_3") (pintype "passive"))
    )
    (net (code "74") (name "unconnected-(X5-Pad4)") (class "Default")
      (node (ref "X5") (pin "4") (pinfunction "4_4") (pintype "passive"))
    )
  )
)
